# uirrc.net
KiCad netlist of a schematic drawn in EAGLE
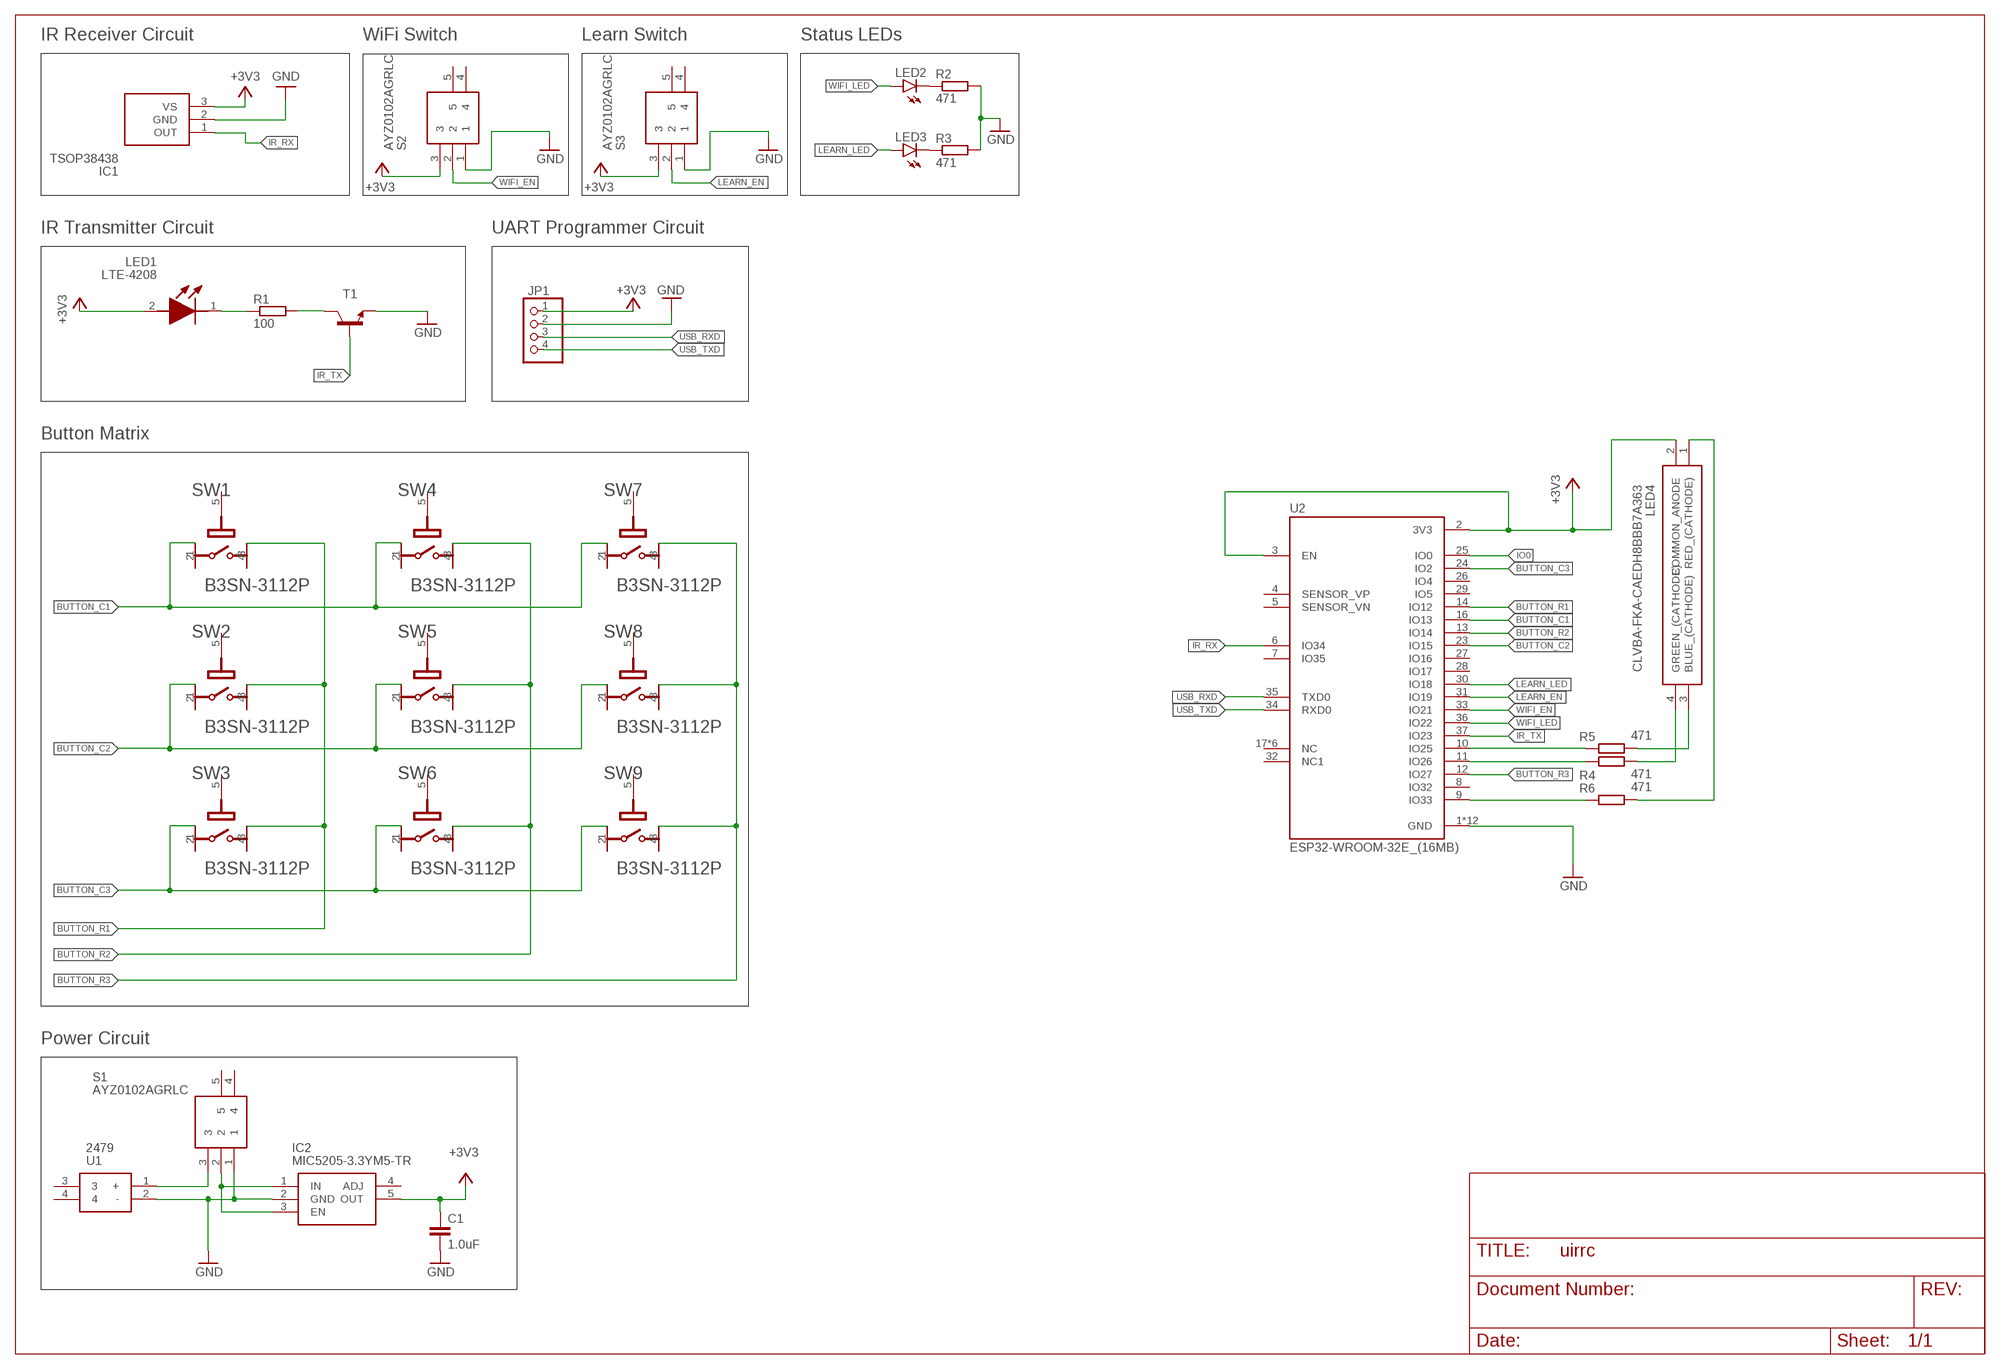
[diagram p0: schematic, sheet 1]

(export (version "E")
  (design (tool "Eeschema 10.0.6"))
  (components
    (comp (ref "C1")
      (value "1.0uF")
      (footprint "eagle-import:C1206")
      (libsource (lib "eagle-import") (part "C-EUC1206"))
    )
    (comp (ref "IC1")
      (value "TSOP38438")
      (footprint "eagle-import:TSOP38238")
      (fields (field (name "MOUSER_PART_NUMBER") "78-TSOP38438"))
      (libsource (lib "eagle-import") (part "TSOP38438"))
    )
    (comp (ref "IC2")
      (value "MIC5205-3.3YM5-TR")
      (footprint "eagle-import:SOT95P280X145-5N")
      (fields (field (name "MOUSER_PART_NUMBER") "998-MIC5205-3.3YM5TR"))
      (libsource (lib "eagle-import") (part "MIC5205-3.3YM5-TR"))
    )
    (comp (ref "JP1")
      (value "PINHD-1X4")
      (footprint "eagle-import:1X04")
      (libsource (lib "eagle-import") (part "PINHD-1X4"))
    )
    (comp (ref "LED1")
      (value "LTE-4208")
      (footprint "eagle-import:LTE4208")
      (fields (field (name "MOUSER_PART_NUMBER") "859-LTE4208"))
      (libsource (lib "eagle-import") (part "LTE-4208"))
    )
    (comp (ref "LED2")
      (value "LEDCHIPLED_1206")
      (footprint "eagle-import:CHIPLED_1206")
      (libsource (lib "eagle-import") (part "LEDCHIPLED_1206"))
    )
    (comp (ref "LED3")
      (value "LEDCHIPLED_1206")
      (footprint "eagle-import:CHIPLED_1206")
      (libsource (lib "eagle-import") (part "LEDCHIPLED_1206"))
    )
    (comp (ref "LED4")
      (value "CLVBA-FKA-CAEDH8BBB7A363")
      (footprint "eagle-import:CLVBAFKACAEDH8BBB7A363")
      (fields (field (name "MOUSER_PART_NUMBER") "941-VBAFKACAEDH8B7A3"))
      (libsource (lib "eagle-import") (part "CLVBA-FKA-CAEDH8BBB7A363"))
    )
    (comp (ref "R1")
      (value "100")
      (footprint "eagle-import:R1206")
      (libsource (lib "eagle-import") (part "R-EU_R1206"))
    )
    (comp (ref "R2")
      (value "471")
      (footprint "eagle-import:R1206")
      (libsource (lib "eagle-import") (part "R-EU_R1206"))
    )
    (comp (ref "R3")
      (value "471")
      (footprint "eagle-import:R1206")
      (libsource (lib "eagle-import") (part "R-EU_R1206"))
    )
    (comp (ref "R4")
      (value "471")
      (footprint "eagle-import:R1206")
      (libsource (lib "eagle-import") (part "R-EU_R1206"))
    )
    (comp (ref "R5")
      (value "471")
      (footprint "eagle-import:R1206")
      (libsource (lib "eagle-import") (part "R-EU_R1206"))
    )
    (comp (ref "R6")
      (value "471")
      (footprint "eagle-import:R1206")
      (libsource (lib "eagle-import") (part "R-EU_R1206"))
    )
    (comp (ref "S1")
      (value "AYZ0102AGRLC")
      (footprint "eagle-import:AYZ0102AGRLC")
      (fields (field (name "MOUSER_PART_NUMBER") "611-AYZ0102AGRLC"))
      (libsource (lib "eagle-import") (part "AYZ0102AGRLC"))
    )
    (comp (ref "S2")
      (value "AYZ0102AGRLC")
      (footprint "eagle-import:AYZ0102AGRLC")
      (fields (field (name "MOUSER_PART_NUMBER") "611-AYZ0102AGRLC"))
      (libsource (lib "eagle-import") (part "AYZ0102AGRLC"))
    )
    (comp (ref "S3")
      (value "AYZ0102AGRLC")
      (footprint "eagle-import:AYZ0102AGRLC")
      (fields (field (name "MOUSER_PART_NUMBER") "611-AYZ0102AGRLC"))
      (libsource (lib "eagle-import") (part "AYZ0102AGRLC"))
    )
    (comp (ref "SW1")
      (value "OMRON_B3SN-3112POMRON_B3SN-3112P_0_0")
      (footprint "eagle-import:OMRON_B3SN-3112P_0")
      (fields
        (field (name "DIGIKEY_PART_NUMBER") "SW262CT-ND")
        (field (name "MF") "Omron")
        (field (name "MOUSER_PART_NUMBER") "653-B3SN-3112P")
      )
      (libsource (lib "eagle-import") (part "OMRON_B3SN-3112POMRON_B3SN-3112P_0_0"))
    )
    (comp (ref "SW2")
      (value "OMRON_B3SN-3112POMRON_B3SN-3112P_0_0")
      (footprint "eagle-import:OMRON_B3SN-3112P_0")
      (fields
        (field (name "DIGIKEY_PART_NUMBER") "SW262CT-ND")
        (field (name "MF") "Omron")
        (field (name "MOUSER_PART_NUMBER") "653-B3SN-3112P")
      )
      (libsource (lib "eagle-import") (part "OMRON_B3SN-3112POMRON_B3SN-3112P_0_0"))
    )
    (comp (ref "SW3")
      (value "OMRON_B3SN-3112POMRON_B3SN-3112P_0_0")
      (footprint "eagle-import:OMRON_B3SN-3112P_0")
      (fields
        (field (name "DIGIKEY_PART_NUMBER") "SW262CT-ND")
        (field (name "MF") "Omron")
        (field (name "MOUSER_PART_NUMBER") "653-B3SN-3112P")
      )
      (libsource (lib "eagle-import") (part "OMRON_B3SN-3112POMRON_B3SN-3112P_0_0"))
    )
    (comp (ref "SW4")
      (value "OMRON_B3SN-3112POMRON_B3SN-3112P_0_0")
      (footprint "eagle-import:OMRON_B3SN-3112P_0")
      (fields
        (field (name "DIGIKEY_PART_NUMBER") "SW262CT-ND")
        (field (name "MF") "Omron")
        (field (name "MOUSER_PART_NUMBER") "653-B3SN-3112P")
      )
      (libsource (lib "eagle-import") (part "OMRON_B3SN-3112POMRON_B3SN-3112P_0_0"))
    )
    (comp (ref "SW5")
      (value "OMRON_B3SN-3112POMRON_B3SN-3112P_0_0")
      (footprint "eagle-import:OMRON_B3SN-3112P_0")
      (fields
        (field (name "DIGIKEY_PART_NUMBER") "SW262CT-ND")
        (field (name "MF") "Omron")
        (field (name "MOUSER_PART_NUMBER") "653-B3SN-3112P")
      )
      (libsource (lib "eagle-import") (part "OMRON_B3SN-3112POMRON_B3SN-3112P_0_0"))
    )
    (comp (ref "SW6")
      (value "OMRON_B3SN-3112POMRON_B3SN-3112P_0_0")
      (footprint "eagle-import:OMRON_B3SN-3112P_0")
      (fields
        (field (name "DIGIKEY_PART_NUMBER") "SW262CT-ND")
        (field (name "MF") "Omron")
        (field (name "MOUSER_PART_NUMBER") "653-B3SN-3112P")
      )
      (libsource (lib "eagle-import") (part "OMRON_B3SN-3112POMRON_B3SN-3112P_0_0"))
    )
    (comp (ref "SW7")
      (value "OMRON_B3SN-3112POMRON_B3SN-3112P_0_0")
      (footprint "eagle-import:OMRON_B3SN-3112P_0")
      (fields
        (field (name "DIGIKEY_PART_NUMBER") "SW262CT-ND")
        (field (name "MF") "Omron")
        (field (name "MOUSER_PART_NUMBER") "653-B3SN-3112P")
      )
      (libsource (lib "eagle-import") (part "OMRON_B3SN-3112POMRON_B3SN-3112P_0_0"))
    )
    (comp (ref "SW8")
      (value "OMRON_B3SN-3112POMRON_B3SN-3112P_0_0")
      (footprint "eagle-import:OMRON_B3SN-3112P_0")
      (fields
        (field (name "DIGIKEY_PART_NUMBER") "SW262CT-ND")
        (field (name "MF") "Omron")
        (field (name "MOUSER_PART_NUMBER") "653-B3SN-3112P")
      )
      (libsource (lib "eagle-import") (part "OMRON_B3SN-3112POMRON_B3SN-3112P_0_0"))
    )
    (comp (ref "SW9")
      (value "OMRON_B3SN-3112POMRON_B3SN-3112P_0_0")
      (footprint "eagle-import:OMRON_B3SN-3112P_0")
      (fields
        (field (name "DIGIKEY_PART_NUMBER") "SW262CT-ND")
        (field (name "MF") "Omron")
        (field (name "MOUSER_PART_NUMBER") "653-B3SN-3112P")
      )
      (libsource (lib "eagle-import") (part "OMRON_B3SN-3112POMRON_B3SN-3112P_0_0"))
    )
    (comp (ref "T1")
      (value "MMBT3904LT1-NPN-SOT23-BEC")
      (footprint "eagle-import:SOT23-BEC")
      (libsource (lib "eagle-import") (part "-NPN-SOT23-BECMMBT3904LT1"))
    )
    (comp (ref "U1")
      (value "2479")
      (footprint "eagle-import:2479")
      (fields (field (name "MOUSER_PART_NUMBER") "534-2479"))
      (libsource (lib "eagle-import") (part "2479"))
    )
    (comp (ref "U2")
      (value "ESP32-WROOM-32E_(16MB)")
      (footprint "eagle-import:XCVR_ESP32-WROOM-32E_(16MB)")
      (fields (field (name "MF") "Espressif Systems") (field (name "MP") "ESP32-WROOM-32E (16MB)"))
      (libsource (lib "eagle-import") (part "ESP32-WROOM-32E_(16MB)"))
    )
  )
  (nets
    (net (code "1") (name "+3V3") (class "Default")
      (node (ref "C1") (pin "1") (pinfunction "1_1") (pintype "passive"))
      (node (ref "IC1") (pin "3") (pinfunction "VS_3") (pintype "bidirectional"))
      (node (ref "IC2") (pin "5") (pinfunction "OUT_5") (pintype "bidirectional"))
      (node (ref "JP1") (pin "1") (pinfunction "1_1") (pintype "passive"))
      (node (ref "LED1") (pin "2") (pinfunction "A_2") (pintype "bidirectional"))
      (node (ref "LED4") (pin "2") (pinfunction "COMMON_ANODE_2") (pintype "bidirectional"))
      (node (ref "S2") (pin "3") (pinfunction "3_3") (pintype "bidirectional"))
      (node (ref "S3") (pin "3") (pinfunction "3_3") (pintype "bidirectional"))
      (node (ref "U2") (pin "2") (pinfunction "3V3_2") (pintype "power_in"))
      (node (ref "U2") (pin "3") (pinfunction "EN_3") (pintype "input"))
    )
    (net (code "2") (name "BUTTON_C1") (class "Default")
      (node (ref "SW1") (pin "1") (pinfunction "1_1") (pintype "passive"))
      (node (ref "SW4") (pin "1") (pinfunction "1_1") (pintype "passive"))
      (node (ref "SW7") (pin "1") (pinfunction "1_1") (pintype "passive"))
      (node (ref "U2") (pin "16") (pinfunction "IO13_16") (pintype "bidirectional"))
    )
    (net (code "3") (name "BUTTON_C2") (class "Default")
      (node (ref "SW2") (pin "1") (pinfunction "1_1") (pintype "passive"))
      (node (ref "SW5") (pin "1") (pinfunction "1_1") (pintype "passive"))
      (node (ref "SW8") (pin "1") (pinfunction "1_1") (pintype "passive"))
      (node (ref "U2") (pin "23") (pinfunction "IO15_23") (pintype "bidirectional"))
    )
    (net (code "4") (name "BUTTON_C3") (class "Default")
      (node (ref "SW3") (pin "1") (pinfunction "1_1") (pintype "passive"))
      (node (ref "SW6") (pin "1") (pinfunction "1_1") (pintype "passive"))
      (node (ref "SW9") (pin "1") (pinfunction "1_1") (pintype "passive"))
      (node (ref "U2") (pin "24") (pinfunction "IO2_24") (pintype "bidirectional"))
    )
    (net (code "5") (name "BUTTON_R1") (class "Default")
      (node (ref "SW1") (pin "3") (pinfunction "3_3") (pintype "passive"))
      (node (ref "SW2") (pin "3") (pinfunction "3_3") (pintype "passive"))
      (node (ref "SW3") (pin "3") (pinfunction "3_3") (pintype "passive"))
      (node (ref "U2") (pin "14") (pinfunction "IO12_14") (pintype "bidirectional"))
    )
    (net (code "6") (name "BUTTON_R2") (class "Default")
      (node (ref "SW4") (pin "3") (pinfunction "3_3") (pintype "passive"))
      (node (ref "SW5") (pin "3") (pinfunction "3_3") (pintype "passive"))
      (node (ref "SW6") (pin "3") (pinfunction "3_3") (pintype "passive"))
      (node (ref "U2") (pin "13") (pinfunction "IO14_13") (pintype "bidirectional"))
    )
    (net (code "7") (name "BUTTON_R3") (class "Default")
      (node (ref "SW7") (pin "3") (pinfunction "3_3") (pintype "passive"))
      (node (ref "SW8") (pin "3") (pinfunction "3_3") (pintype "passive"))
      (node (ref "SW9") (pin "3") (pinfunction "3_3") (pintype "passive"))
      (node (ref "U2") (pin "12") (pinfunction "IO27_12") (pintype "bidirectional"))
    )
    (net (code "8") (name "GND") (class "Default")
      (node (ref "C1") (pin "2") (pinfunction "2_2") (pintype "passive"))
      (node (ref "IC1") (pin "2") (pinfunction "GND_2") (pintype "bidirectional"))
      (node (ref "IC2") (pin "2") (pinfunction "GND_2") (pintype "bidirectional"))
      (node (ref "JP1") (pin "2") (pinfunction "2_2") (pintype "passive"))
      (node (ref "R2") (pin "2") (pinfunction "2_2") (pintype "passive"))
      (node (ref "R3") (pin "2") (pinfunction "2_2") (pintype "passive"))
      (node (ref "S1") (pin "1") (pinfunction "1_1") (pintype "bidirectional"))
      (node (ref "S2") (pin "1") (pinfunction "1_1") (pintype "bidirectional"))
      (node (ref "S3") (pin "1") (pinfunction "1_1") (pintype "bidirectional"))
      (node (ref "T1") (pin "E") (pinfunction "E_E") (pintype "passive"))
      (node (ref "U1") (pin "2") (pinfunction "-_2") (pintype "bidirectional"))
      (node (ref "U2") (pin "1") (pinfunction "GND_1") (pintype "power_in"))
      (node (ref "U2") (pin "15") (pinfunction "GND_15") (pintype "power_in"))
      (node (ref "U2") (pin "38") (pinfunction "GND_38") (pintype "power_in"))
      (node (ref "U2") (pin "39_1") (pinfunction "GND_39_1") (pintype "power_in"))
      (node (ref "U2") (pin "39_2") (pinfunction "GND_39_2") (pintype "power_in"))
      (node (ref "U2") (pin "39_3") (pinfunction "GND_39_3") (pintype "power_in"))
      (node (ref "U2") (pin "39_4") (pinfunction "GND_39_4") (pintype "power_in"))
      (node (ref "U2") (pin "39_5") (pinfunction "GND_39_5") (pintype "power_in"))
      (node (ref "U2") (pin "39_6") (pinfunction "GND_39_6") (pintype "power_in"))
      (node (ref "U2") (pin "39_7") (pinfunction "GND_39_7") (pintype "power_in"))
      (node (ref "U2") (pin "39_8") (pinfunction "GND_39_8") (pintype "power_in"))
      (node (ref "U2") (pin "39_9") (pinfunction "GND_39_9") (pintype "power_in"))
    )
    (net (code "9") (name "IO0") (class "Default")
      (node (ref "U2") (pin "25") (pinfunction "IO0_25") (pintype "bidirectional"))
    )
    (net (code "10") (name "IR_RX") (class "Default")
      (node (ref "IC1") (pin "1") (pinfunction "OUT_1") (pintype "bidirectional"))
      (node (ref "U2") (pin "6") (pinfunction "IO34_6") (pintype "input"))
    )
    (net (code "11") (name "IR_TX") (class "Default")
      (node (ref "T1") (pin "B") (pinfunction "B_B") (pintype "passive"))
      (node (ref "U2") (pin "37") (pinfunction "IO23_37") (pintype "bidirectional"))
    )
    (net (code "12") (name "LEARN_EN") (class "Default")
      (node (ref "S3") (pin "2") (pinfunction "2_2") (pintype "bidirectional"))
      (node (ref "U2") (pin "31") (pinfunction "IO19_31") (pintype "bidirectional"))
    )
    (net (code "13") (name "LEARN_LED") (class "Default")
      (node (ref "LED3") (pin "A") (pinfunction "A_A") (pintype "passive"))
      (node (ref "U2") (pin "30") (pinfunction "IO18_30") (pintype "bidirectional"))
    )
    (net (code "14") (name "Net-(IC2-EN)") (class "Default")
      (node (ref "IC2") (pin "1") (pinfunction "IN_1") (pintype "bidirectional"))
      (node (ref "IC2") (pin "3") (pinfunction "EN_3") (pintype "bidirectional"))
      (node (ref "S1") (pin "2") (pinfunction "2_2") (pintype "bidirectional"))
    )
    (net (code "15") (name "Net-(LED1-K)") (class "Default")
      (node (ref "LED1") (pin "1") (pinfunction "K_1") (pintype "bidirectional"))
      (node (ref "R1") (pin "1") (pinfunction "1_1") (pintype "passive"))
    )
    (net (code "16") (name "Net-(LED2-PadC)") (class "Default")
      (node (ref "LED2") (pin "C") (pinfunction "C_C") (pintype "passive"))
      (node (ref "R2") (pin "1") (pinfunction "1_1") (pintype "passive"))
    )
    (net (code "17") (name "Net-(LED3-PadC)") (class "Default")
      (node (ref "LED3") (pin "C") (pinfunction "C_C") (pintype "passive"))
      (node (ref "R3") (pin "1") (pinfunction "1_1") (pintype "passive"))
    )
    (net (code "18") (name "Net-(LED4-BLUE_(CATHODE))") (class "Default")
      (node (ref "LED4") (pin "3") (pinfunction "BLUE_(CATHODE)_3") (pintype "bidirectional"))
      (node (ref "R5") (pin "2") (pinfunction "2_2") (pintype "passive"))
    )
    (net (code "19") (name "Net-(LED4-GREEN_(CATHODE))") (class "Default")
      (node (ref "LED4") (pin "4") (pinfunction "GREEN_(CATHODE)_4") (pintype "bidirectional"))
      (node (ref "R4") (pin "2") (pinfunction "2_2") (pintype "passive"))
    )
    (net (code "20") (name "Net-(LED4-RED_(CATHODE))") (class "Default")
      (node (ref "LED4") (pin "1") (pinfunction "RED_(CATHODE)_1") (pintype "bidirectional"))
      (node (ref "R6") (pin "2") (pinfunction "2_2") (pintype "passive"))
    )
    (net (code "21") (name "Net-(R1-Pad2)") (class "Default")
      (node (ref "R1") (pin "2") (pinfunction "2_2") (pintype "passive"))
      (node (ref "T1") (pin "C") (pinfunction "C_C") (pintype "passive"))
    )
    (net (code "22") (name "Net-(U1-+)") (class "Default")
      (node (ref "S1") (pin "3") (pinfunction "3_3") (pintype "bidirectional"))
      (node (ref "U1") (pin "1") (pinfunction "+_1") (pintype "bidirectional"))
    )
    (net (code "23") (name "Net-(U2-IO25)") (class "Default")
      (node (ref "R5") (pin "1") (pinfunction "1_1") (pintype "passive"))
      (node (ref "U2") (pin "10") (pinfunction "IO25_10") (pintype "bidirectional"))
    )
    (net (code "24") (name "Net-(U2-IO26)") (class "Default")
      (node (ref "R4") (pin "1") (pinfunction "1_1") (pintype "passive"))
      (node (ref "U2") (pin "11") (pinfunction "IO26_11") (pintype "bidirectional"))
    )
    (net (code "25") (name "Net-(U2-IO33)") (class "Default")
      (node (ref "R6") (pin "1") (pinfunction "1_1") (pintype "passive"))
      (node (ref "U2") (pin "9") (pinfunction "IO33_9") (pintype "bidirectional"))
    )
    (net (code "26") (name "USB_RXD") (class "Default")
      (node (ref "JP1") (pin "3") (pinfunction "3_3") (pintype "passive"))
      (node (ref "U2") (pin "35") (pinfunction "TXD0_35") (pintype "bidirectional"))
    )
    (net (code "27") (name "USB_TXD") (class "Default")
      (node (ref "JP1") (pin "4") (pinfunction "4_4") (pintype "passive"))
      (node (ref "U2") (pin "34") (pinfunction "RXD0_34") (pintype "bidirectional"))
    )
    (net (code "28") (name "WIFI_EN") (class "Default")
      (node (ref "S2") (pin "2") (pinfunction "2_2") (pintype "bidirectional"))
      (node (ref "U2") (pin "33") (pinfunction "IO21_33") (pintype "bidirectional"))
    )
    (net (code "29") (name "WIFI_LED") (class "Default")
      (node (ref "LED2") (pin "A") (pinfunction "A_A") (pintype "passive"))
      (node (ref "U2") (pin "36") (pinfunction "IO22_36") (pintype "bidirectional"))
    )
    (net (code "30") (name "unconnected-(IC2-ADJ-Pad4)") (class "Default")
      (node (ref "IC2") (pin "4") (pinfunction "ADJ_4") (pintype "bidirectional"))
    )
    (net (code "31") (name "unconnected-(S1-Pad4)") (class "Default")
      (node (ref "S1") (pin "4") (pinfunction "4_4") (pintype "bidirectional"))
    )
    (net (code "32") (name "unconnected-(S1-Pad5)") (class "Default")
      (node (ref "S1") (pin "5") (pinfunction "5_5") (pintype "bidirectional"))
    )
    (net (code "33") (name "unconnected-(S2-Pad4)") (class "Default")
      (node (ref "S2") (pin "4") (pinfunction "4_4") (pintype "bidirectional"))
    )
    (net (code "34") (name "unconnected-(S2-Pad5)") (class "Default")
      (node (ref "S2") (pin "5") (pinfunction "5_5") (pintype "bidirectional"))
    )
    (net (code "35") (name "unconnected-(S3-Pad4)") (class "Default")
      (node (ref "S3") (pin "4") (pinfunction "4_4") (pintype "bidirectional"))
    )
    (net (code "36") (name "unconnected-(S3-Pad5)") (class "Default")
      (node (ref "S3") (pin "5") (pinfunction "5_5") (pintype "bidirectional"))
    )
    (net (code "37") (name "unconnected-(SW1-Pad2)") (class "Default")
      (node (ref "SW1") (pin "2") (pinfunction "2_2") (pintype "passive"))
    )
    (net (code "38") (name "unconnected-(SW1-Pad4)") (class "Default")
      (node (ref "SW1") (pin "4") (pinfunction "4_4") (pintype "passive"))
    )
    (net (code "39") (name "unconnected-(SW1-Pad5)") (class "Default")
      (node (ref "SW1") (pin "5") (pinfunction "5_5") (pintype "passive"))
    )
    (net (code "40") (name "unconnected-(SW2-Pad2)") (class "Default")
      (node (ref "SW2") (pin "2") (pinfunction "2_2") (pintype "passive"))
    )
    (net (code "41") (name "unconnected-(SW2-Pad4)") (class "Default")
      (node (ref "SW2") (pin "4") (pinfunction "4_4") (pintype "passive"))
    )
    (net (code "42") (name "unconnected-(SW2-Pad5)") (class "Default")
      (node (ref "SW2") (pin "5") (pinfunction "5_5") (pintype "passive"))
    )
    (net (code "43") (name "unconnected-(SW3-Pad2)") (class "Default")
      (node (ref "SW3") (pin "2") (pinfunction "2_2") (pintype "passive"))
    )
    (net (code "44") (name "unconnected-(SW3-Pad4)") (class "Default")
      (node (ref "SW3") (pin "4") (pinfunction "4_4") (pintype "passive"))
    )
    (net (code "45") (name "unconnected-(SW3-Pad5)") (class "Default")
      (node (ref "SW3") (pin "5") (pinfunction "5_5") (pintype "passive"))
    )
    (net (code "46") (name "unconnected-(SW4-Pad2)") (class "Default")
      (node (ref "SW4") (pin "2") (pinfunction "2_2") (pintype "passive"))
    )
    (net (code "47") (name "unconnected-(SW4-Pad4)") (class "Default")
      (node (ref "SW4") (pin "4") (pinfunction "4_4") (pintype "passive"))
    )
    (net (code "48") (name "unconnected-(SW4-Pad5)") (class "Default")
      (node (ref "SW4") (pin "5") (pinfunction "5_5") (pintype "passive"))
    )
    (net (code "49") (name "unconnected-(SW5-Pad2)") (class "Default")
      (node (ref "SW5") (pin "2") (pinfunction "2_2") (pintype "passive"))
    )
    (net (code "50") (name "unconnected-(SW5-Pad4)") (class "Default")
      (node (ref "SW5") (pin "4") (pinfunction "4_4") (pintype "passive"))
    )
    (net (code "51") (name "unconnected-(SW5-Pad5)") (class "Default")
      (node (ref "SW5") (pin "5") (pinfunction "5_5") (pintype "passive"))
    )
    (net (code "52") (name "unconnected-(SW6-Pad2)") (class "Default")
      (node (ref "SW6") (pin "2") (pinfunction "2_2") (pintype "passive"))
    )
    (net (code "53") (name "unconnected-(SW6-Pad4)") (class "Default")
      (node (ref "SW6") (pin "4") (pinfunction "4_4") (pintype "passive"))
    )
    (net (code "54") (name "unconnected-(SW6-Pad5)") (class "Default")
      (node (ref "SW6") (pin "5") (pinfunction "5_5") (pintype "passive"))
    )
    (net (code "55") (name "unconnected-(SW7-Pad2)") (class "Default")
      (node (ref "SW7") (pin "2") (pinfunction "2_2") (pintype "passive"))
    )
    (net (code "56") (name "unconnected-(SW7-Pad4)") (class "Default")
      (node (ref "SW7") (pin "4") (pinfunction "4_4") (pintype "passive"))
    )
    (net (code "57") (name "unconnected-(SW7-Pad5)") (class "Default")
      (node (ref "SW7") (pin "5") (pinfunction "5_5") (pintype "passive"))
    )
    (net (code "58") (name "unconnected-(SW8-Pad2)") (class "Default")
      (node (ref "SW8") (pin "2") (pinfunction "2_2") (pintype "passive"))
    )
    (net (code "59") (name "unconnected-(SW8-Pad4)") (class "Default")
      (node (ref "SW8") (pin "4") (pinfunction "4_4") (pintype "passive"))
    )
    (net (code "60") (name "unconnected-(SW8-Pad5)") (class "Default")
      (node (ref "SW8") (pin "5") (pinfunction "5_5") (pintype "passive"))
    )
    (net (code "61") (name "unconnected-(SW9-Pad2)") (class "Default")
      (node (ref "SW9") (pin "2") (pinfunction "2_2") (pintype "passive"))
    )
    (net (code "62") (name "unconnected-(SW9-Pad4)") (class "Default")
      (node (ref "SW9") (pin "4") (pinfunction "4_4") (pintype "passive"))
    )
    (net (code "63") (name "unconnected-(SW9-Pad5)") (class "Default")
      (node (ref "SW9") (pin "5") (pinfunction "5_5") (pintype "passive"))
    )
    (net (code "64") (name "unconnected-(U1-Pad3)") (class "Default")
      (node (ref "U1") (pin "3") (pinfunction "3_3") (pintype "bidirectional"))
    )
    (net (code "65") (name "unconnected-(U1-Pad4)") (class "Default")
      (node (ref "U1") (pin "4") (pinfunction "4_4") (pintype "bidirectional"))
    )
    (net (code "66") (name "unconnected-(U2-IO4-Pad26)") (class "Default")
      (node (ref "U2") (pin "26") (pinfunction "IO4_26") (pintype "bidirectional"))
    )
    (net (code "67") (name "unconnected-(U2-IO5-Pad29)") (class "Default")
      (node (ref "U2") (pin "29") (pinfunction "IO5_29") (pintype "bidirectional"))
    )
    (net (code "68") (name "unconnected-(U2-IO16-Pad27)") (class "Default")
      (node (ref "U2") (pin "27") (pinfunction "IO16_27") (pintype "bidirectional"))
    )
    (net (code "69") (name "unconnected-(U2-IO17-Pad28)") (class "Default")
      (node (ref "U2") (pin "28") (pinfunction "IO17_28") (pintype "bidirectional"))
    )
    (net (code "70") (name "unconnected-(U2-IO32-Pad8)") (class "Default")
      (node (ref "U2") (pin "8") (pinfunction "IO32_8") (pintype "bidirectional"))
    )
    (net (code "71") (name "unconnected-(U2-IO35-Pad7)") (class "Default")
      (node (ref "U2") (pin "7") (pinfunction "IO35_7") (pintype "input"))
    )
    (net (code "72") (name "unconnected-(U2-NC-Pad17)") (class "Default")
      (node (ref "U2") (pin "17") (pinfunction "NC_17") (pintype "no_connect"))
    )
    (net (code "73") (name "unconnected-(U2-NC-Pad18)") (class "Default")
      (node (ref "U2") (pin "18") (pinfunction "NC_18") (pintype "no_connect"))
    )
    (net (code "74") (name "unconnected-(U2-NC-Pad19)") (class "Default")
      (node (ref "U2") (pin "19") (pinfunction "NC_19") (pintype "no_connect"))
    )
    (net (code "75") (name "unconnected-(U2-NC-Pad20)") (class "Default")
      (node (ref "U2") (pin "20") (pinfunction "NC_20") (pintype "no_connect"))
    )
    (net (code "76") (name "unconnected-(U2-NC-Pad21)") (class "Default")
      (node (ref "U2") (pin "21") (pinfunction "NC_21") (pintype "no_connect"))
    )
    (net (code "77") (name "unconnected-(U2-NC-Pad22)") (class "Default")
      (node (ref "U2") (pin "22") (pinfunction "NC_22") (pintype "no_connect"))
    )
    (net (code "78") (name "unconnected-(U2-NC1-Pad32)") (class "Default")
      (node (ref "U2") (pin "32") (pinfunction "NC1_32") (pintype "no_connect"))
    )
    (net (code "79") (name "unconnected-(U2-SENSOR_VN-Pad5)") (class "Default")
      (node (ref "U2") (pin "5") (pinfunction "SENSOR_VN_5") (pintype "input"))
    )
    (net (code "80") (name "unconnected-(U2-SENSOR_VP-Pad4)") (class "Default")
      (node (ref "U2") (pin "4") (pinfunction "SENSOR_VP_4") (pintype "input"))
    )
  )
)
